# Power_Distribution_-_Front_Enclosure.net
KiCad netlist of a schematic drawn in Altium Designer
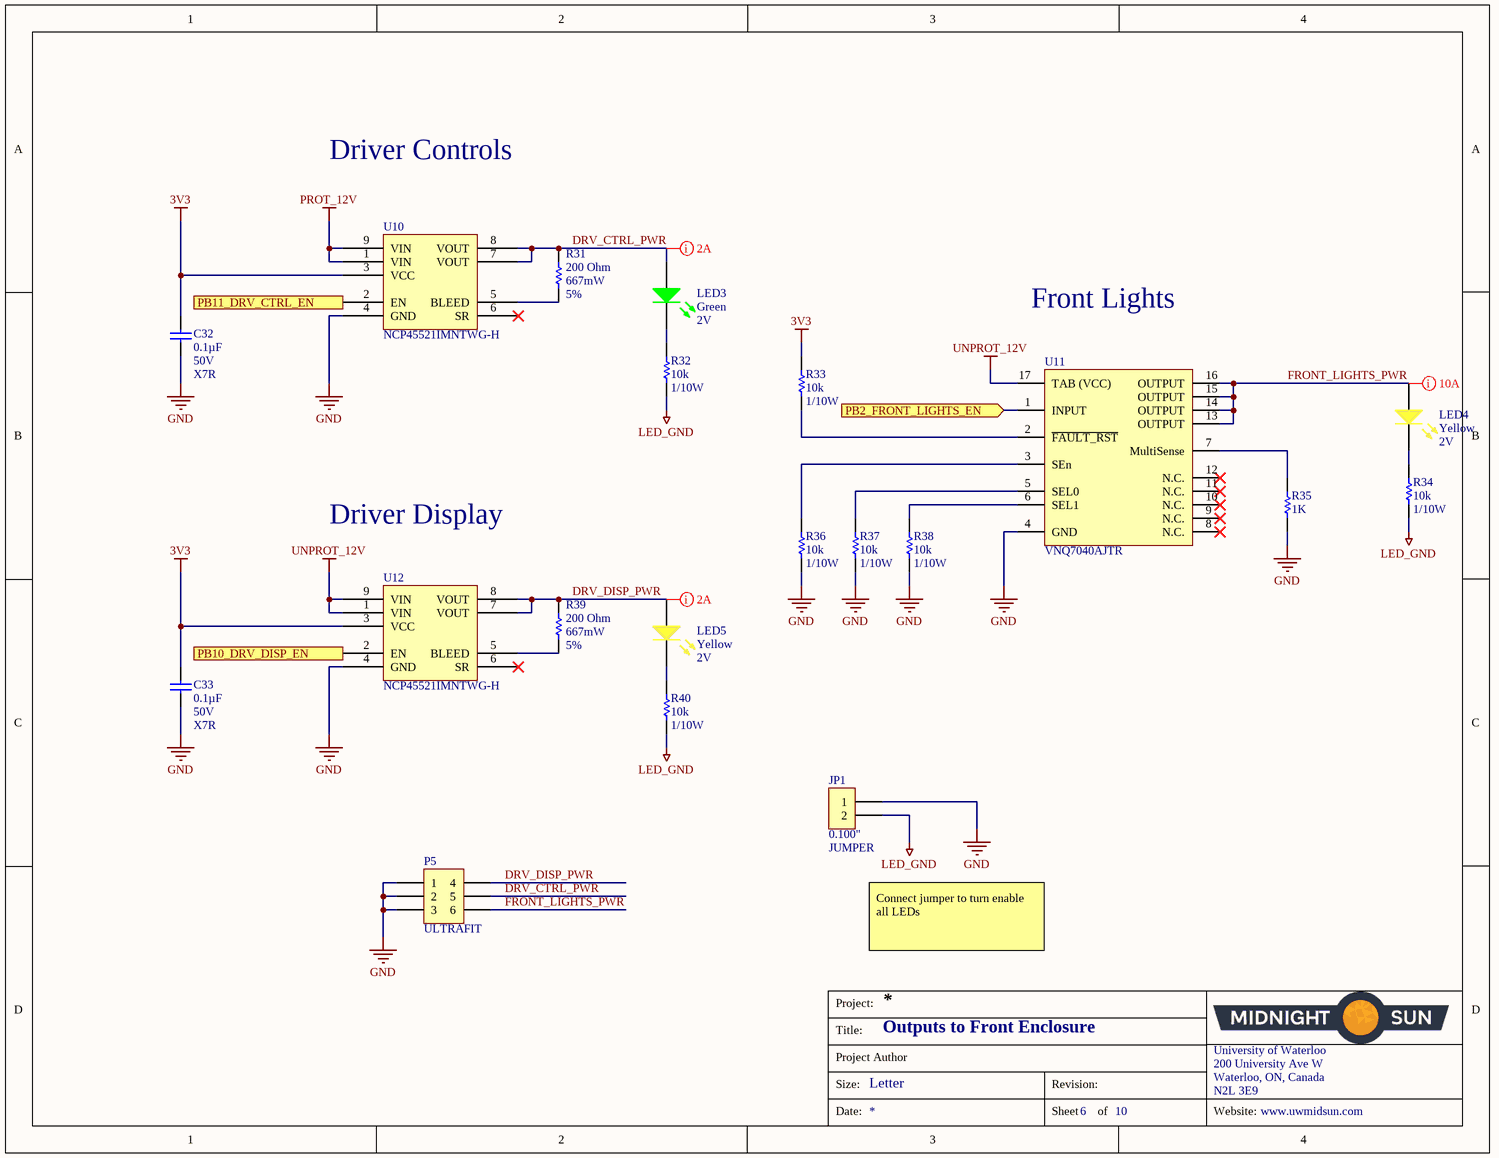
[diagram p0: Power Distribution - Front Enclosure.SchDoc]

(export (version "E")
  (design (tool "Eeschema 10.0.6"))
  (components
    (comp (ref "C32")
      (value "CAP CER 0.1UF 50V 10% X7R 0603")
      (footprint "CAP, 0603")
      (description "0.10µF ±10% 50V Ceramic Capacitor X7R 0603 (1608 Metric)")
      (fields
        (field (name "TOLERANCE") "±10%")
        (field (name "CAPACITANCE") "0.1µF")
        (field (name "VOLTAGE") "50V")
        (field (name "TEMPERATURE COEFFICIENT") "X7R")
      )
      (libsource (lib "Schematic Diagrams") (part "CAP CER 0.1UF 50V 10% X7R 0603"))
    )
    (comp (ref "C33")
      (value "CAP CER 0.1UF 50V 10% X7R 0603")
      (footprint "CAP, 0603")
      (description "0.10µF ±10% 50V Ceramic Capacitor X7R 0603 (1608 Metric)")
      (fields
        (field (name "TOLERANCE") "±10%")
        (field (name "CAPACITANCE") "0.1µF")
        (field (name "VOLTAGE") "50V")
        (field (name "TEMPERATURE COEFFICIENT") "X7R")
      )
      (libsource (lib "Schematic Diagrams") (part "CAP CER 0.1UF 50V 10% X7R 0603"))
    )
    (comp (ref "JP1")
      (value "JUMPER")
      (footprint "CONN 2POS JUMPER 0.1\"")
      (description "2 Positions Header Connector Through Hole Gold")
      (fields
        (field (name "MANUFACTURER") "Omron Electronics Inc-EMC Div")
        (field (name "MANUFACTURER PART NUMBER") "XG8T-0231")
        (field (name "ROW SPACING - MATING") "0.100\"")
        (field (name "TYPE") "JUMPER")
      )
      (libsource (lib "Schematic Diagrams") (part "CONN 2POS JUMPER 0.1{dblquote}"))
    )
    (comp (ref "LED3")
      (value "LED GREEN CLEAR 2V 0603")
      (footprint "LED_0603")
      (description "Green 572nm LED Indication - Discrete 2V 0603 (1608 Metric)")
      (fields
        (field (name "MANUFACTURER") "Wurth Electronics Inc.")
        (field (name "MANUFACTURER PART NUMBER") "150060VS75000")
        (field (name "COLOR") "Green")
        (field (name "VOLTAGE - FORWARD (VF) (TYP)") "2V")
      )
      (libsource (lib "Schematic Diagrams") (part "LED GREEN CLEAR 2V 0603"))
    )
    (comp (ref "LED4")
      (value "LED YELLOW CLEAR 2.1V 0603")
      (footprint "LED_0603")
      (description "Yellow 590nm LED Indication - Discrete 2V 0603 (1608 Metric)")
      (fields
        (field (name "MANUFACTURER") "Wurth Electronics Inc.")
        (field (name "MANUFACTURER PART NUMBER") "150060YS75000")
        (field (name "COLOR") "Yellow")
        (field (name "VOLTAGE - FORWARD (VF) (TYP)") "2V")
      )
      (libsource (lib "Schematic Diagrams") (part "LED YELLOW CLEAR 2.1V 0603"))
    )
    (comp (ref "LED5")
      (value "LED YELLOW CLEAR 2.1V 0603")
      (footprint "LED_0603")
      (description "Yellow 590nm LED Indication - Discrete 2V 0603 (1608 Metric)")
      (fields
        (field (name "MANUFACTURER") "Wurth Electronics Inc.")
        (field (name "MANUFACTURER PART NUMBER") "150060YS75000")
        (field (name "COLOR") "Yellow")
        (field (name "VOLTAGE - FORWARD (VF) (TYP)") "2V")
      )
      (libsource (lib "Schematic Diagrams") (part "LED YELLOW CLEAR 2.1V 0603"))
    )
    (comp (ref "P5")
      (value "CONN 6POS ULTRA-FIT 0.138\"")
      (footprint "CONN, 6POS ULTRA-FIT")
      (description "6 Positions Header Connector 0.138\" (3.50mm) Through Hole Tin")
      (fields (field (name "VOLTAGE") "400V") (field (name "SERIES") "ULTRAFIT"))
      (libsource (lib "Schematic Diagrams") (part "CONN 6POS ULTRA-FIT 0.138{dblquote}"))
    )
    (comp (ref "R31")
      (value "200 Ohm")
      (footprint "RES 1206")
      (fields
        (field (name "MANUFACTURER") "Panasonic")
        (field (name "MANUFACTURER PART NUMBER") "ERJ-P08J201V")
        (field (name "TOLERANCE") "5%")
        (field (name "MAX POWER DISSIPATION") "667mW")
      )
      (libsource (lib "Schematic Diagrams") (part "RES 200 OHM 5% 2/3W 1206"))
    )
    (comp (ref "R32")
      (value "RES 10K OHM 1% 1/10W 0603")
      (footprint "RES, 0603")
      (description "RES SMD 10K OHM 1% 1/10W 0603")
      (fields
        (field (name "TOLERANCE") "±1%")
        (field (name "RESISTANCE") "10k")
        (field (name "POWER") "1/10W")
      )
      (libsource (lib "Schematic Diagrams") (part "RES 10K OHM 1% 1/10W 0603"))
    )
    (comp (ref "R33")
      (value "RES 10K OHM 1% 1/10W 0603")
      (footprint "RES, 0603")
      (description "RES SMD 10K OHM 1% 1/10W 0603")
      (fields
        (field (name "TOLERANCE") "±1%")
        (field (name "RESISTANCE") "10k")
        (field (name "POWER") "1/10W")
      )
      (libsource (lib "Schematic Diagrams") (part "RES 10K OHM 1% 1/10W 0603"))
    )
    (comp (ref "R34")
      (value "RES 10K OHM 1% 1/10W 0603")
      (footprint "RES, 0603")
      (description "RES SMD 10K OHM 1% 1/10W 0603")
      (fields
        (field (name "TOLERANCE") "±1%")
        (field (name "RESISTANCE") "10k")
        (field (name "POWER") "1/10W")
      )
      (libsource (lib "Schematic Diagrams") (part "RES 10K OHM 1% 1/10W 0603"))
    )
    (comp (ref "R35")
      (value "1K")
      (footprint "RES, 0603")
      (description "1k Ohm ±5% 0.1W, 1/10W Chip Resistor 0603 (1608 Metric)")
      (fields
        (field (name "MANUFACTURER") "Yageo")
        (field (name "MANUFACTURER PART NUMBER") "RC0603JR-071KL")
      )
      (libsource (lib "Schematic Diagrams") (part "RES 1K OHM 5% 1/10W 0603"))
    )
    (comp (ref "R36")
      (value "RES 10K OHM 1% 1/10W 0603")
      (footprint "RES, 0603")
      (description "RES SMD 10K OHM 1% 1/10W 0603")
      (fields
        (field (name "TOLERANCE") "±1%")
        (field (name "RESISTANCE") "10k")
        (field (name "POWER") "1/10W")
      )
      (libsource (lib "Schematic Diagrams") (part "RES 10K OHM 1% 1/10W 0603"))
    )
    (comp (ref "R37")
      (value "RES 10K OHM 1% 1/10W 0603")
      (footprint "RES, 0603")
      (description "RES SMD 10K OHM 1% 1/10W 0603")
      (fields
        (field (name "TOLERANCE") "±1%")
        (field (name "RESISTANCE") "10k")
        (field (name "POWER") "1/10W")
      )
      (libsource (lib "Schematic Diagrams") (part "RES 10K OHM 1% 1/10W 0603"))
    )
    (comp (ref "R38")
      (value "RES 10K OHM 1% 1/10W 0603")
      (footprint "RES, 0603")
      (description "RES SMD 10K OHM 1% 1/10W 0603")
      (fields
        (field (name "TOLERANCE") "±1%")
        (field (name "RESISTANCE") "10k")
        (field (name "POWER") "1/10W")
      )
      (libsource (lib "Schematic Diagrams") (part "RES 10K OHM 1% 1/10W 0603"))
    )
    (comp (ref "R39")
      (value "200 Ohm")
      (footprint "RES 1206")
      (fields
        (field (name "MANUFACTURER") "Panasonic")
        (field (name "MANUFACTURER PART NUMBER") "ERJ-P08J201V")
        (field (name "TOLERANCE") "5%")
        (field (name "MAX POWER DISSIPATION") "667mW")
      )
      (libsource (lib "Schematic Diagrams") (part "RES 200 OHM 5% 2/3W 1206"))
    )
    (comp (ref "R40")
      (value "RES 10K OHM 1% 1/10W 0603")
      (footprint "RES, 0603")
      (description "RES SMD 10K OHM 1% 1/10W 0603")
      (fields
        (field (name "TOLERANCE") "±1%")
        (field (name "RESISTANCE") "10k")
        (field (name "POWER") "1/10W")
      )
      (libsource (lib "Schematic Diagrams") (part "RES 10K OHM 1% 1/10W 0603"))
    )
    (comp (ref "U10")
      (value "IC LOAD SWITCH ACT-HI 10.5A 8DFN")
      (footprint "IC LOAD SWITCH ACT-HI 10.5A 8DFN")
      (description "NCP45521IMNTWG-H")
      (fields
        (field (name "MANUFACTURER") "ON Semiconductor")
        (field (name "MANUFACTURER PART NUMBER") "NCP45521IMNTWG-H")
      )
      (libsource (lib "Schematic Diagrams") (part "IC LOAD SWITCH ACT-HI 10.5A 8DFN"))
    )
    (comp (ref "U11")
      (value "VNQ7040AJTR")
      (footprint "IC DVR HIGH-SIDE 1CH POWERSSO-16")
      (description "IC, High Side Drive, 4V - 28V, 24A, 40 mOhm")
      (libsource (lib "Schematic Diagrams") (part "IC DVR HIGH-SIDE 1CH POWERSSO-16"))
    )
    (comp (ref "U12")
      (value "IC LOAD SWITCH ACT-HI 10.5A 8DFN")
      (footprint "IC LOAD SWITCH ACT-HI 10.5A 8DFN")
      (description "NCP45521IMNTWG-H")
      (fields
        (field (name "MANUFACTURER") "ON Semiconductor")
        (field (name "MANUFACTURER PART NUMBER") "NCP45521IMNTWG-H")
      )
      (libsource (lib "Schematic Diagrams") (part "IC LOAD SWITCH ACT-HI 10.5A 8DFN"))
    )
  )
  (nets
    (net (code "1") (name "/DRV_CTRL_PWR") (class "Default")
      (node (ref "LED3") (pin "1") (pinfunction "A_1") (pintype "passive"))
      (node (ref "P5") (pin "5") (pinfunction "5_5") (pintype "passive"))
      (node (ref "R31") (pin "1") (pinfunction "1_1") (pintype "passive"))
      (node (ref "U10") (pin "7") (pinfunction "VOUT_7") (pintype "passive"))
      (node (ref "U10") (pin "8") (pinfunction "VOUT_8") (pintype "passive"))
    )
    (net (code "2") (name "/DRV_DISP_PWR") (class "Default")
      (node (ref "LED5") (pin "1") (pinfunction "A_1") (pintype "passive"))
      (node (ref "P5") (pin "4") (pinfunction "4_4") (pintype "passive"))
      (node (ref "R39") (pin "1") (pinfunction "1_1") (pintype "passive"))
      (node (ref "U12") (pin "7") (pinfunction "VOUT_7") (pintype "passive"))
      (node (ref "U12") (pin "8") (pinfunction "VOUT_8") (pintype "passive"))
    )
    (net (code "3") (name "/FRONT_LIGHTS_PWR") (class "Default")
      (node (ref "LED4") (pin "1") (pinfunction "A_1") (pintype "passive"))
      (node (ref "P5") (pin "6") (pinfunction "6_6") (pintype "passive"))
      (node (ref "U11") (pin "13") (pinfunction "OUTPUT_13") (pintype "passive"))
      (node (ref "U11") (pin "14") (pinfunction "OUTPUT_14") (pintype "passive"))
      (node (ref "U11") (pin "15") (pinfunction "OUTPUT_15") (pintype "passive"))
      (node (ref "U11") (pin "16") (pinfunction "OUTPUT_16") (pintype "passive"))
    )
    (net (code "4") (name "/PB2_FRONT_LIGHTS_EN") (class "Default")
      (node (ref "U11") (pin "1") (pinfunction "INPUT_1") (pintype "passive"))
    )
    (net (code "5") (name "/PB10_DRV_DISP_EN") (class "Default")
      (node (ref "U12") (pin "2") (pinfunction "EN_2") (pintype "passive"))
    )
    (net (code "6") (name "/PB11_DRV_CTRL_EN") (class "Default")
      (node (ref "U10") (pin "2") (pinfunction "EN_2") (pintype "passive"))
    )
    (net (code "7") (name "3V3") (class "Default")
      (node (ref "C32") (pin "1") (pinfunction "1_1") (pintype "passive"))
      (node (ref "C33") (pin "1") (pinfunction "1_1") (pintype "passive"))
      (node (ref "R33") (pin "1") (pinfunction "1_1") (pintype "passive"))
      (node (ref "U10") (pin "3") (pinfunction "VCC_3") (pintype "passive"))
      (node (ref "U12") (pin "3") (pinfunction "VCC_3") (pintype "passive"))
    )
    (net (code "8") (name "GND") (class "Default")
      (node (ref "C32") (pin "2") (pinfunction "2_2") (pintype "passive"))
      (node (ref "C33") (pin "2") (pinfunction "2_2") (pintype "passive"))
      (node (ref "JP1") (pin "1") (pinfunction "1_1") (pintype "passive"))
      (node (ref "P5") (pin "1") (pinfunction "1_1") (pintype "passive"))
      (node (ref "P5") (pin "2") (pinfunction "2_2") (pintype "passive"))
      (node (ref "P5") (pin "3") (pinfunction "3_3") (pintype "passive"))
      (node (ref "R35") (pin "2") (pinfunction "2_2") (pintype "passive"))
      (node (ref "R36") (pin "2") (pinfunction "2_2") (pintype "passive"))
      (node (ref "R37") (pin "2") (pinfunction "2_2") (pintype "passive"))
      (node (ref "R38") (pin "2") (pinfunction "2_2") (pintype "passive"))
      (node (ref "U10") (pin "4") (pinfunction "GND_4") (pintype "passive"))
      (node (ref "U11") (pin "4") (pinfunction "GND_4") (pintype "passive"))
      (node (ref "U12") (pin "4") (pinfunction "GND_4") (pintype "passive"))
    )
    (net (code "9") (name "LED_GND") (class "Default")
      (node (ref "JP1") (pin "2") (pinfunction "2_2") (pintype "passive"))
      (node (ref "R32") (pin "2") (pinfunction "2_2") (pintype "passive"))
      (node (ref "R34") (pin "2") (pinfunction "2_2") (pintype "passive"))
      (node (ref "R40") (pin "2") (pinfunction "2_2") (pintype "passive"))
    )
    (net (code "10") (name "Net-(LED3-K)") (class "Default")
      (node (ref "LED3") (pin "2") (pinfunction "K_2") (pintype "passive"))
      (node (ref "R32") (pin "1") (pinfunction "1_1") (pintype "passive"))
    )
    (net (code "11") (name "Net-(LED4-K)") (class "Default")
      (node (ref "LED4") (pin "2") (pinfunction "K_2") (pintype "passive"))
      (node (ref "R34") (pin "1") (pinfunction "1_1") (pintype "passive"))
    )
    (net (code "12") (name "Net-(LED5-K)") (class "Default")
      (node (ref "LED5") (pin "2") (pinfunction "K_2") (pintype "passive"))
      (node (ref "R40") (pin "1") (pinfunction "1_1") (pintype "passive"))
    )
    (net (code "13") (name "Net-(U10-BLEED)") (class "Default")
      (node (ref "R31") (pin "2") (pinfunction "2_2") (pintype "passive"))
      (node (ref "U10") (pin "5") (pinfunction "BLEED_5") (pintype "passive"))
    )
    (net (code "14") (name "Net-(U11-MultiSense)") (class "Default")
      (node (ref "R35") (pin "1") (pinfunction "1_1") (pintype "passive"))
      (node (ref "U11") (pin "7") (pinfunction "MultiSense_7") (pintype "passive"))
    )
    (net (code "15") (name "Net-(U11-SEL0)") (class "Default")
      (node (ref "R37") (pin "1") (pinfunction "1_1") (pintype "passive"))
      (node (ref "U11") (pin "5") (pinfunction "SEL0_5") (pintype "passive"))
    )
    (net (code "16") (name "Net-(U11-SEL1)") (class "Default")
      (node (ref "R38") (pin "1") (pinfunction "1_1") (pintype "passive"))
      (node (ref "U11") (pin "6") (pinfunction "SEL1_6") (pintype "passive"))
    )
    (net (code "17") (name "Net-(U11-SEn)") (class "Default")
      (node (ref "R36") (pin "1") (pinfunction "1_1") (pintype "passive"))
      (node (ref "U11") (pin "3") (pinfunction "SEn_3") (pintype "passive"))
    )
    (net (code "18") (name "Net-(U11-~{FAULT_RST})") (class "Default")
      (node (ref "R33") (pin "2") (pinfunction "2_2") (pintype "passive"))
      (node (ref "U11") (pin "2") (pinfunction "~{FAULT_RST}_2") (pintype "passive"))
    )
    (net (code "19") (name "Net-(U12-BLEED)") (class "Default")
      (node (ref "R39") (pin "2") (pinfunction "2_2") (pintype "passive"))
      (node (ref "U12") (pin "5") (pinfunction "BLEED_5") (pintype "passive"))
    )
    (net (code "20") (name "PROT_12V") (class "Default")
      (node (ref "U10") (pin "1") (pinfunction "VIN_1") (pintype "passive"))
      (node (ref "U10") (pin "9") (pinfunction "VIN_9") (pintype "passive"))
    )
    (net (code "21") (name "UNPROT_12V") (class "Default")
      (node (ref "U11") (pin "17") (pinfunction "TAB_(VCC)_17") (pintype "passive"))
      (node (ref "U12") (pin "1") (pinfunction "VIN_1") (pintype "passive"))
      (node (ref "U12") (pin "9") (pinfunction "VIN_9") (pintype "passive"))
    )
    (net (code "22") (name "unconnected-(U10-SR-Pad6)") (class "Default")
      (node (ref "U10") (pin "6") (pinfunction "SR_6") (pintype "passive+no_connect"))
    )
    (net (code "23") (name "unconnected-(U11-N.C.-Pad8)") (class "Default")
      (node (ref "U11") (pin "8") (pinfunction "N.C._8") (pintype "passive+no_connect"))
    )
    (net (code "24") (name "unconnected-(U11-N.C.-Pad9)") (class "Default")
      (node (ref "U11") (pin "9") (pinfunction "N.C._9") (pintype "passive+no_connect"))
    )
    (net (code "25") (name "unconnected-(U11-N.C.-Pad10)") (class "Default")
      (node (ref "U11") (pin "10") (pinfunction "N.C._10") (pintype "passive+no_connect"))
    )
    (net (code "26") (name "unconnected-(U11-N.C.-Pad11)") (class "Default")
      (node (ref "U11") (pin "11") (pinfunction "N.C._11") (pintype "passive+no_connect"))
    )
    (net (code "27") (name "unconnected-(U11-N.C.-Pad12)") (class "Default")
      (node (ref "U11") (pin "12") (pinfunction "N.C._12") (pintype "passive+no_connect"))
    )
    (net (code "28") (name "unconnected-(U12-SR-Pad6)") (class "Default")
      (node (ref "U12") (pin "6") (pinfunction "SR_6") (pintype "passive+no_connect"))
    )
  )
)
